# 01_-_MC.net
KiCad netlist of a schematic drawn in Altium Designer
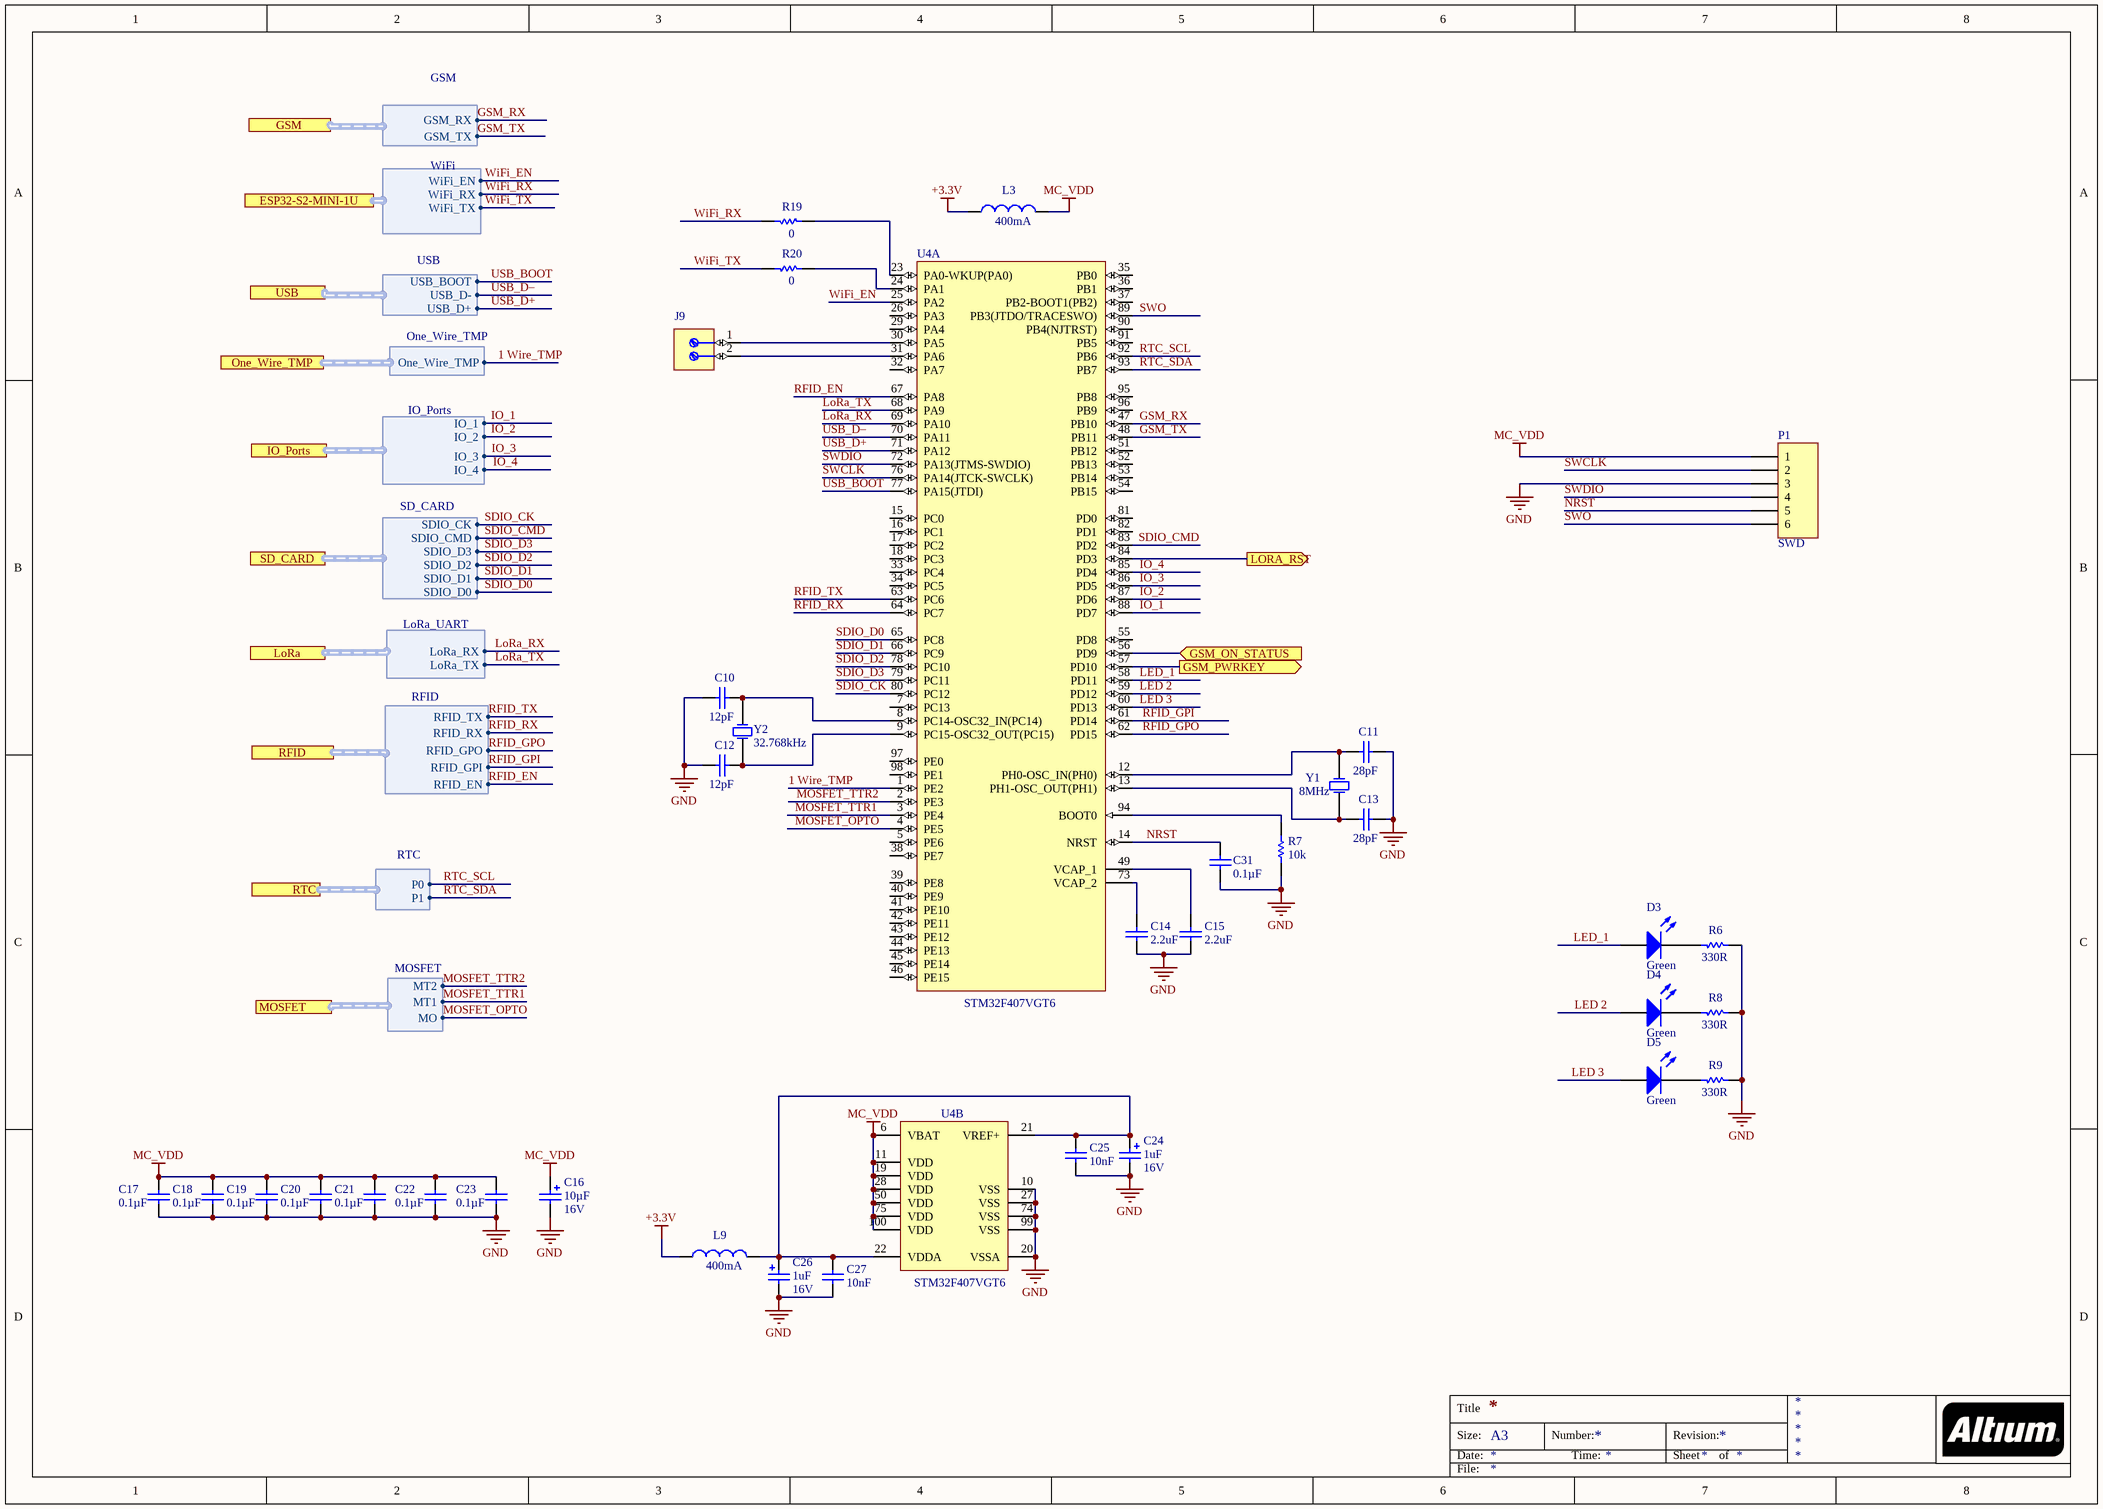
[diagram p0: [01] - MC.SchDoc]

(export (version "E")
  (design (tool "Eeschema 10.0.6"))
  (components
    (comp (ref "C10")
      (value "Capacitor")
      (footprint "Cap 0603")
      (description "Chip Capacitor Nonpolar")
      (fields
        (field (name "MANUFACTURER") "KEMET")
        (field (name "MANUFACTURER PART NUMBER") "C0603C120J5GAC-TU")
        (field (name "CAPACITANCE") "12pF")
      )
      (libsource (lib "Altium_Library") (part "Capacitor"))
    )
    (comp (ref "C11")
      (value "Capacitor")
      (footprint "Cap 0603")
      (description "Chip Capacitor Nonpolar")
      (fields
        (field (name "MANUFACTURER") "KEMET")
        (field (name "MANUFACTURER PART NUMBER") "C0603C180K5GACTU")
        (field (name "CAPACITANCE") "28pF")
      )
      (libsource (lib "Altium_Library") (part "Capacitor"))
    )
    (comp (ref "C12")
      (value "Capacitor")
      (footprint "Cap 0603")
      (description "Chip Capacitor Nonpolar")
      (fields
        (field (name "MANUFACTURER") "KEMET")
        (field (name "MANUFACTURER PART NUMBER") "C0603C120J5GAC-TU")
        (field (name "CAPACITANCE") "12pF")
      )
      (libsource (lib "Altium_Library") (part "Capacitor"))
    )
    (comp (ref "C13")
      (value "Capacitor")
      (footprint "Cap 0603")
      (description "Chip Capacitor Nonpolar")
      (fields
        (field (name "MANUFACTURER") "KEMET")
        (field (name "MANUFACTURER PART NUMBER") "C0603C180K5GACTU")
        (field (name "CAPACITANCE") "28pF")
      )
      (libsource (lib "Altium_Library") (part "Capacitor"))
    )
    (comp (ref "C14")
      (value "Capacitor")
      (footprint "Cap 0603")
      (description "Chip Capacitor Nonpolar")
      (fields
        (field (name "MANUFACTURER") "Samsung")
        (field (name "MANUFACTURER PART NUMBER") "CL21A225KAFNNNG")
        (field (name "CAPACITANCE") "2.2uF")
      )
      (libsource (lib "Altium_Library") (part "Capacitor"))
    )
    (comp (ref "C15")
      (value "Capacitor")
      (footprint "Cap 0603")
      (description "Chip Capacitor Nonpolar")
      (fields
        (field (name "MANUFACTURER") "Samsung")
        (field (name "MANUFACTURER PART NUMBER") "CL21A225KAFNNNG")
        (field (name "CAPACITANCE") "2.2uF")
      )
      (libsource (lib "Altium_Library") (part "Capacitor"))
    )
    (comp (ref "C16")
      (value "Capacitor Polarized")
      (footprint "Tantalum 3216 A")
      (description "Tantalum Capacitor")
      (fields
        (field (name "MANUFACTURER") "Kemet")
        (field (name "MANUFACTURER PART NUMBER") "T491A106K016AT")
        (field (name "CAPACITANCE") "10µF")
        (field (name "VOLTAGE - RATED") "16V")
      )
      (libsource (lib "Altium_Library") (part "Capacitor Polarized"))
    )
    (comp (ref "C17")
      (value "Capacitor")
      (footprint "Cap 0603")
      (description "Chip Capacitor Nonpolar")
      (fields
        (field (name "MANUFACTURER") "Kemet")
        (field (name "MANUFACTURER PART NUMBER") "C0603C104K5RACTU")
        (field (name "CAPACITANCE") "0.1µF")
      )
      (libsource (lib "Altium_Library") (part "Capacitor"))
    )
    (comp (ref "C18")
      (value "Capacitor")
      (footprint "Cap 0603")
      (description "Chip Capacitor Nonpolar")
      (fields
        (field (name "MANUFACTURER") "Kemet")
        (field (name "MANUFACTURER PART NUMBER") "C0603C104K5RACTU")
        (field (name "CAPACITANCE") "0.1µF")
      )
      (libsource (lib "Altium_Library") (part "Capacitor"))
    )
    (comp (ref "C19")
      (value "Capacitor")
      (footprint "Cap 0603")
      (description "Chip Capacitor Nonpolar")
      (fields
        (field (name "MANUFACTURER") "Kemet")
        (field (name "MANUFACTURER PART NUMBER") "C0603C104K5RACTU")
        (field (name "CAPACITANCE") "0.1µF")
      )
      (libsource (lib "Altium_Library") (part "Capacitor"))
    )
    (comp (ref "C20")
      (value "Capacitor")
      (footprint "Cap 0603")
      (description "Chip Capacitor Nonpolar")
      (fields
        (field (name "MANUFACTURER") "Kemet")
        (field (name "MANUFACTURER PART NUMBER") "C0603C104K5RACTU")
        (field (name "CAPACITANCE") "0.1µF")
      )
      (libsource (lib "Altium_Library") (part "Capacitor"))
    )
    (comp (ref "C21")
      (value "Capacitor")
      (footprint "Cap 0603")
      (description "Chip Capacitor Nonpolar")
      (fields
        (field (name "MANUFACTURER") "Kemet")
        (field (name "MANUFACTURER PART NUMBER") "C0603C104K5RACTU")
        (field (name "CAPACITANCE") "0.1µF")
      )
      (libsource (lib "Altium_Library") (part "Capacitor"))
    )
    (comp (ref "C22")
      (value "Capacitor")
      (footprint "Cap 0603")
      (description "Chip Capacitor Nonpolar")
      (fields
        (field (name "MANUFACTURER") "Kemet")
        (field (name "MANUFACTURER PART NUMBER") "C0603C104K5RACTU")
        (field (name "CAPACITANCE") "0.1µF")
      )
      (libsource (lib "Altium_Library") (part "Capacitor"))
    )
    (comp (ref "C23")
      (value "Capacitor")
      (footprint "Cap 0603")
      (description "Chip Capacitor Nonpolar")
      (fields
        (field (name "MANUFACTURER") "Kemet")
        (field (name "MANUFACTURER PART NUMBER") "C0603C104K5RACTU")
        (field (name "CAPACITANCE") "0.1µF")
      )
      (libsource (lib "Altium_Library") (part "Capacitor"))
    )
    (comp (ref "C24")
      (value "Capacitor Polarized")
      (footprint "Tantalum 3216 A")
      (description "Tantalum Capacitor")
      (fields
        (field (name "MANUFACTURER") "Vishay Sprague")
        (field (name "MANUFACTURER PART NUMBER") "293D105X9016A2TE3")
        (field (name "CAPACITANCE") "1uF")
        (field (name "VOLTAGE RATING") "16V")
      )
      (libsource (lib "Altium_Library") (part "Capacitor Polarized"))
    )
    (comp (ref "C25")
      (value "Capacitor")
      (footprint "Cap 0603")
      (description "Chip Capacitor Nonpolar")
      (fields
        (field (name "MANUFACTURER") "Samsung")
        (field (name "MANUFACTURER PART NUMBER") "CL10B103KB8WPNC")
        (field (name "CAPACITANCE") "10nF")
      )
      (libsource (lib "Altium_Library") (part "Capacitor"))
    )
    (comp (ref "C26")
      (value "Capacitor Polarized")
      (footprint "Tantalum 3216 A")
      (description "Tantalum Capacitor")
      (fields
        (field (name "MANUFACTURER") "Vishay Sprague")
        (field (name "MANUFACTURER PART NUMBER") "293D105X9016A2TE3")
        (field (name "CAPACITANCE") "1uF")
        (field (name "VOLTAGE RATING") "16V")
      )
      (libsource (lib "Altium_Library") (part "Capacitor Polarized"))
    )
    (comp (ref "C27")
      (value "Capacitor")
      (footprint "Cap 0603")
      (description "Chip Capacitor Nonpolar")
      (fields
        (field (name "MANUFACTURER") "Samsung")
        (field (name "MANUFACTURER PART NUMBER") "CL10B103KB8WPNC")
        (field (name "CAPACITANCE") "10nF")
      )
      (libsource (lib "Altium_Library") (part "Capacitor"))
    )
    (comp (ref "C31")
      (value "Capacitor")
      (footprint "Cap 0603")
      (description "Chip Capacitor Nonpolar")
      (fields
        (field (name "MANUFACTURER") "Kemet")
        (field (name "MANUFACTURER PART NUMBER") "C0603C104K5RACTU")
        (field (name "CAPACITANCE") "0.1µF")
      )
      (libsource (lib "Altium_Library") (part "Capacitor"))
    )
    (comp (ref "D3")
      (value "LED")
      (footprint "Led 0805 green")
      (description "Led 0805")
      (fields
        (field (name "MANUFACTURER") "Vishay Lite-On")
        (field (name "MANUFACTURER PART NUMBER") "LTST-S220GKT")
        (field (name "COLOUR") "Green")
      )
      (libsource (lib "Altium_Library") (part "LED"))
    )
    (comp (ref "D4")
      (value "LED")
      (footprint "Led 0805 green")
      (description "Led 0805")
      (fields
        (field (name "MANUFACTURER") "Vishay Lite-On")
        (field (name "MANUFACTURER PART NUMBER") "LTST-S220GKT")
        (field (name "COLOUR") "Green")
      )
      (libsource (lib "Altium_Library") (part "LED"))
    )
    (comp (ref "D5")
      (value "LED")
      (footprint "Led 0805 green")
      (description "Led 0805")
      (fields
        (field (name "MANUFACTURER") "Vishay Lite-On")
        (field (name "MANUFACTURER PART NUMBER") "LTST-S220GKT")
        (field (name "COLOUR") "Green")
      )
      (libsource (lib "Altium_Library") (part "LED"))
    )
    (comp (ref "J9")
      (value "~")
      (footprint "Blue Tractor-2021:Connector -PHOENIX_1715721")
      (description "Terminal Block, 2 Positions, Screw Connection")
      (fields
        (field (name "PART NUMBER") "PHOENIX_1715721")
        (field (name "MANUFACTURER") "PHOENIX CONTACT")
        (field (name "AUTHOR") "CERN DEM JLC")
      )
      (libsource (lib "Connectors") (part "Terminal Block_2 Positions_Screw Connection"))
    )
    (comp (ref "L3")
      (value "Inductor")
      (footprint "0603")
      (description "Sumida inductore ferrite core smd")
      (fields
        (field (name "MANUFACTURER") "Murata Electronics North America")
        (field (name "MANUFACTURER PART NUMBER") "BLM18AG102SN1D")
        (field (name "CURRENT RATING (MAX)") "400mA")
      )
      (libsource (lib "Altium_Library") (part "Inductor"))
    )
    (comp (ref "L9")
      (value "Inductor")
      (footprint "0603")
      (description "Sumida inductore ferrite core smd")
      (fields
        (field (name "MANUFACTURER") "Murata Electronics North America")
        (field (name "MANUFACTURER PART NUMBER") "BLM18AG102SN1D")
        (field (name "CURRENT RATING (MAX)") "400mA")
      )
      (libsource (lib "Altium_Library") (part "Inductor"))
    )
    (comp (ref "P1")
      (value "SWD")
      (footprint "HDR1X6")
      (description "Header, 6-Pin")
      (fields (field (name "PUBLISHER") "Altium Limited"))
      (libsource (lib "Miscellaneous Connectors") (part "Header 6"))
    )
    (comp (ref "R6")
      (value "Res1")
      (footprint "Res-0603")
      (description "Chip Resistor")
      (fields
        (field (name "MANUFACTURER") "Panasonic")
        (field (name "MANUFACTURER PART NUMBER") "ERJ-3EKF3300V")
        (field (name "RESISTANCE") "330R")
      )
      (libsource (lib "Altium_Library") (part "Res1"))
    )
    (comp (ref "R7")
      (value "Res1")
      (footprint "Res-0603")
      (description "Chip Resistor")
      (fields
        (field (name "MANUFACTURER") "Panasonic")
        (field (name "MANUFACTURER PART NUMBER") "ERJ-3GEYJ103V")
        (field (name "RESISTANCE") "10k")
      )
      (libsource (lib "Altium_Library") (part "Res1"))
    )
    (comp (ref "R8")
      (value "Res1")
      (footprint "Res-0603")
      (description "Chip Resistor")
      (fields
        (field (name "MANUFACTURER") "Panasonic")
        (field (name "MANUFACTURER PART NUMBER") "ERJ-3EKF3300V")
        (field (name "RESISTANCE") "330R")
      )
      (libsource (lib "Altium_Library") (part "Res1"))
    )
    (comp (ref "R9")
      (value "Res1")
      (footprint "Res-0603")
      (description "Chip Resistor")
      (fields
        (field (name "MANUFACTURER") "Panasonic")
        (field (name "MANUFACTURER PART NUMBER") "ERJ-3EKF3300V")
        (field (name "RESISTANCE") "330R")
      )
      (libsource (lib "Altium_Library") (part "Res1"))
    )
    (comp (ref "R19")
      (value "Res1")
      (footprint "Res-0603")
      (description "Chip Resistor")
      (fields
        (field (name "MANUFACTURER") "Panasonic")
        (field (name "MANUFACTURER PART NUMBER") "ERJ-3EKF3300V")
        (field (name "RESISTANCE") "0")
      )
      (libsource (lib "Altium_Library") (part "Res1"))
    )
    (comp (ref "R20")
      (value "Res1")
      (footprint "Res-0603")
      (description "Chip Resistor")
      (fields
        (field (name "MANUFACTURER") "Panasonic")
        (field (name "MANUFACTURER PART NUMBER") "ERJ-3EKF3300V")
        (field (name "RESISTANCE") "0")
      )
      (libsource (lib "Altium_Library") (part "Res1"))
    )
    (comp (ref "U4")
      (value "STM32F407VGT6J")
      (footprint "LQFP100_N")
      (fields
        (field (name "MANUFACTURER") "STMicroelectronics")
        (field (name "MANUFACTURER PART NUMBER") "STM32F407VGT6")
      )
      (libsource (lib "STMicroelectronics STM32 F4") (part "STM32F407VGT6J"))
    )
    (comp (ref "Y1")
      (value "XTAL2pin")
      (footprint "ABM3")
      (description "Crystal Oscillator")
      (fields
        (field (name "MANUFACTURER") "Abracon Corporation")
        (field (name "MANUFACTURER PART NUMBER") "ABM3-8.000MHZ-D2Y-T")
        (field (name "FREQUENCY") "8MHz")
        (field (name "PUBLISHER") "Ruslan Gimazetdinov")
      )
      (libsource (lib "Altium_Library") (part "XTAL2pin"))
    )
    (comp (ref "Y2")
      (value "32768")
      (footprint "ECX-31B")
      (description "Crystal Oscillator")
      (fields
        (field (name "MANUFACTURER") "ECS International")
        (field (name "MANUFACTURER PART NUMBER") "ECS-.327-12.5-34B-TR")
        (field (name "FREQUENCY") "32.768kHz")
      )
      (libsource (lib "Altium_Library") (part "XTAL2pin"))
    )
  )
  (nets
    (net (code "11") (name "+3.3V") (class "Default")
      (node (ref "L3") (pin "1") (pinfunction "1_1") (pintype "passive"))
      (node (ref "L9") (pin "1") (pinfunction "1_1") (pintype "passive"))
    )
    (net (code "12") (name "/1 Wire_TMP") (class "Default")
      (node (ref "U4") (pin "1") (pinfunction "PE2_1") (pintype "bidirectional"))
    )
    (net (code "13") (name "/GSM_ON_STATUS") (class "Default")
      (node (ref "U4") (pin "56") (pinfunction "PD9_56") (pintype "bidirectional"))
    )
    (net (code "14") (name "/GSM_PWRKEY") (class "Default")
      (node (ref "U4") (pin "57") (pinfunction "PD10_57") (pintype "bidirectional"))
    )
    (net (code "15") (name "/GSM_RX") (class "Default")
      (node (ref "U4") (pin "47") (pinfunction "PB10_47") (pintype "bidirectional"))
    )
    (net (code "16") (name "/GSM_TX") (class "Default")
      (node (ref "U4") (pin "48") (pinfunction "PB11_48") (pintype "bidirectional"))
    )
    (net (code "17") (name "/IO_1") (class "Default")
      (node (ref "U4") (pin "88") (pinfunction "PD7_88") (pintype "bidirectional"))
    )
    (net (code "18") (name "/IO_2") (class "Default")
      (node (ref "U4") (pin "87") (pinfunction "PD6_87") (pintype "bidirectional"))
    )
    (net (code "19") (name "/IO_3") (class "Default")
      (node (ref "U4") (pin "86") (pinfunction "PD5_86") (pintype "bidirectional"))
    )
    (net (code "20") (name "/IO_4") (class "Default")
      (node (ref "U4") (pin "85") (pinfunction "PD4_85") (pintype "bidirectional"))
    )
    (net (code "21") (name "/LED 2") (class "Default")
      (node (ref "D4") (pin "2") (pinfunction "A_2") (pintype "passive"))
      (node (ref "U4") (pin "59") (pinfunction "PD12_59") (pintype "bidirectional"))
    )
    (net (code "22") (name "/LED 3") (class "Default")
      (node (ref "D5") (pin "2") (pinfunction "A_2") (pintype "passive"))
      (node (ref "U4") (pin "60") (pinfunction "PD13_60") (pintype "bidirectional"))
    )
    (net (code "23") (name "/LED_1") (class "Default")
      (node (ref "D3") (pin "2") (pinfunction "A_2") (pintype "passive"))
      (node (ref "U4") (pin "58") (pinfunction "PD11_58") (pintype "bidirectional"))
    )
    (net (code "24") (name "/LORA_RST") (class "Default")
      (node (ref "U4") (pin "84") (pinfunction "PD3_84") (pintype "bidirectional"))
    )
    (net (code "25") (name "/LoRa_RX") (class "Default")
      (node (ref "U4") (pin "69") (pinfunction "PA10_69") (pintype "bidirectional"))
    )
    (net (code "26") (name "/LoRa_TX") (class "Default")
      (node (ref "U4") (pin "68") (pinfunction "PA9_68") (pintype "bidirectional"))
    )
    (net (code "27") (name "/MOSFET_OPTO") (class "Default")
      (node (ref "U4") (pin "4") (pinfunction "PE5_4") (pintype "bidirectional"))
    )
    (net (code "28") (name "/MOSFET_TTR1") (class "Default")
      (node (ref "U4") (pin "3") (pinfunction "PE4_3") (pintype "bidirectional"))
    )
    (net (code "29") (name "/MOSFET_TTR2") (class "Default")
      (node (ref "U4") (pin "2") (pinfunction "PE3_2") (pintype "bidirectional"))
    )
    (net (code "30") (name "/NRST") (class "Default")
      (node (ref "C31") (pin "2") (pinfunction "2_2") (pintype "passive"))
      (node (ref "P1") (pin "5") (pinfunction "5_5") (pintype "passive"))
      (node (ref "U4") (pin "14") (pinfunction "NRST_14") (pintype "bidirectional"))
    )
    (net (code "31") (name "/RFID_EN") (class "Default")
      (node (ref "U4") (pin "67") (pinfunction "PA8_67") (pintype "bidirectional"))
    )
    (net (code "32") (name "/RFID_GPI") (class "Default")
      (node (ref "U4") (pin "61") (pinfunction "PD14_61") (pintype "bidirectional"))
    )
    (net (code "33") (name "/RFID_GPO") (class "Default")
      (node (ref "U4") (pin "62") (pinfunction "PD15_62") (pintype "bidirectional"))
    )
    (net (code "34") (name "/RFID_RX") (class "Default")
      (node (ref "U4") (pin "64") (pinfunction "PC7_64") (pintype "bidirectional"))
    )
    (net (code "35") (name "/RFID_TX") (class "Default")
      (node (ref "U4") (pin "63") (pinfunction "PC6_63") (pintype "bidirectional"))
    )
    (net (code "36") (name "/RTC_SCL") (class "Default")
      (node (ref "U4") (pin "92") (pinfunction "PB6_92") (pintype "bidirectional"))
    )
    (net (code "37") (name "/RTC_SDA") (class "Default")
      (node (ref "U4") (pin "93") (pinfunction "PB7_93") (pintype "bidirectional"))
    )
    (net (code "38") (name "/SDIO_CK") (class "Default")
      (node (ref "U4") (pin "80") (pinfunction "PC12_80") (pintype "bidirectional"))
    )
    (net (code "39") (name "/SDIO_CMD") (class "Default")
      (node (ref "U4") (pin "83") (pinfunction "PD2_83") (pintype "bidirectional"))
    )
    (net (code "40") (name "/SDIO_D0") (class "Default")
      (node (ref "U4") (pin "65") (pinfunction "PC8_65") (pintype "bidirectional"))
    )
    (net (code "41") (name "/SDIO_D1") (class "Default")
      (node (ref "U4") (pin "66") (pinfunction "PC9_66") (pintype "bidirectional"))
    )
    (net (code "42") (name "/SDIO_D2") (class "Default")
      (node (ref "U4") (pin "78") (pinfunction "PC10_78") (pintype "bidirectional"))
    )
    (net (code "43") (name "/SDIO_D3") (class "Default")
      (node (ref "U4") (pin "79") (pinfunction "PC11_79") (pintype "bidirectional"))
    )
    (net (code "44") (name "/SWCLK") (class "Default")
      (node (ref "P1") (pin "2") (pinfunction "2_2") (pintype "passive"))
      (node (ref "U4") (pin "76") (pinfunction "PA14(JTCK-SWCLK)_76") (pintype "bidirectional"))
    )
    (net (code "45") (name "/SWDIO") (class "Default")
      (node (ref "P1") (pin "4") (pinfunction "4_4") (pintype "passive"))
      (node (ref "U4") (pin "72") (pinfunction "PA13(JTMS-SWDIO)_72") (pintype "bidirectional"))
    )
    (net (code "46") (name "/SWO") (class "Default")
      (node (ref "P1") (pin "6") (pinfunction "6_6") (pintype "passive"))
      (node (ref "U4") (pin "89") (pinfunction "PB3(JTDO/TRACESWO)_89") (pintype "bidirectional"))
    )
    (net (code "47") (name "/USB_BOOT") (class "Default")
      (node (ref "U4") (pin "77") (pinfunction "PA15(JTDI)_77") (pintype "bidirectional"))
    )
    (net (code "48") (name "/USB_D+") (class "Default")
      (node (ref "U4") (pin "71") (pinfunction "PA12_71") (pintype "bidirectional"))
    )
    (net (code "49") (name "/USB_D–") (class "Default")
      (node (ref "U4") (pin "70") (pinfunction "PA11_70") (pintype "bidirectional"))
    )
    (net (code "50") (name "/WiFi_EN") (class "Default")
      (node (ref "U4") (pin "25") (pinfunction "PA2_25") (pintype "bidirectional"))
    )
    (net (code "51") (name "/WiFi_RX") (class "Default")
      (node (ref "R19") (pin "1") (pinfunction "1_1") (pintype "passive"))
    )
    (net (code "52") (name "/WiFi_TX") (class "Default")
      (node (ref "R20") (pin "1") (pinfunction "1_1") (pintype "passive"))
    )
    (net (code "63") (name "GND") (class "Default")
      (node (ref "C10") (pin "2") (pinfunction "2_2") (pintype "passive"))
      (node (ref "C11") (pin "2") (pinfunction "2_2") (pintype "passive"))
      (node (ref "C12") (pin "2") (pinfunction "2_2") (pintype "passive"))
      (node (ref "C13") (pin "2") (pinfunction "2_2") (pintype "passive"))
      (node (ref "C14") (pin "1") (pinfunction "1_1") (pintype "passive"))
      (node (ref "C15") (pin "1") (pinfunction "1_1") (pintype "passive"))
      (node (ref "C16") (pin "2") (pinfunction "2_2") (pintype "passive"))
      (node (ref "C17") (pin "1") (pinfunction "1_1") (pintype "passive"))
      (node (ref "C18") (pin "1") (pinfunction "1_1") (pintype "passive"))
      (node (ref "C19") (pin "1") (pinfunction "1_1") (pintype "passive"))
      (node (ref "C20") (pin "1") (pinfunction "1_1") (pintype "passive"))
      (node (ref "C21") (pin "1") (pinfunction "1_1") (pintype "passive"))
      (node (ref "C22") (pin "1") (pinfunction "1_1") (pintype "passive"))
      (node (ref "C23") (pin "1") (pinfunction "1_1") (pintype "passive"))
      (node (ref "C24") (pin "2") (pinfunction "2_2") (pintype "passive"))
      (node (ref "C25") (pin "1") (pinfunction "1_1") (pintype "passive"))
      (node (ref "C26") (pin "2") (pinfunction "2_2") (pintype "passive"))
      (node (ref "C27") (pin "1") (pinfunction "1_1") (pintype "passive"))
      (node (ref "C31") (pin "1") (pinfunction "1_1") (pintype "passive"))
      (node (ref "P1") (pin "3") (pinfunction "3_3") (pintype "passive"))
      (node (ref "R6") (pin "2") (pinfunction "2_2") (pintype "passive"))
      (node (ref "R7") (pin "1") (pinfunction "1_1") (pintype "passive"))
      (node (ref "R8") (pin "2") (pinfunction "2_2") (pintype "passive"))
      (node (ref "R9") (pin "2") (pinfunction "2_2") (pintype "passive"))
      (node (ref "U4") (pin "10") (pinfunction "VSS_10") (pintype "power_in"))
      (node (ref "U4") (pin "20") (pinfunction "VSSA_20") (pintype "power_in"))
      (node (ref "U4") (pin "27") (pinfunction "VSS_27") (pintype "power_in"))
      (node (ref "U4") (pin "74") (pinfunction "VSS_74") (pintype "power_in"))
      (node (ref "U4") (pin "99") (pinfunction "VSS_99") (pintype "power_in"))
    )
    (net (code "64") (name "MC_VDD") (class "Default")
      (node (ref "C16") (pin "1") (pinfunction "1_1") (pintype "passive"))
      (node (ref "C17") (pin "2") (pinfunction "2_2") (pintype "passive"))
      (node (ref "C18") (pin "2") (pinfunction "2_2") (pintype "passive"))
      (node (ref "C19") (pin "2") (pinfunction "2_2") (pintype "passive"))
      (node (ref "C20") (pin "2") (pinfunction "2_2") (pintype "passive"))
      (node (ref "C21") (pin "2") (pinfunction "2_2") (pintype "passive"))
      (node (ref "C22") (pin "2") (pinfunction "2_2") (pintype "passive"))
      (node (ref "C23") (pin "2") (pinfunction "2_2") (pintype "passive"))
      (node (ref "L3") (pin "2") (pinfunction "2_2") (pintype "passive"))
      (node (ref "P1") (pin "1") (pinfunction "1_1") (pintype "passive"))
      (node (ref "U4") (pin "100") (pinfunction "VDD_100") (pintype "power_in"))
      (node (ref "U4") (pin "11") (pinfunction "VDD_11") (pintype "power_in"))
      (node (ref "U4") (pin "19") (pinfunction "VDD_19") (pintype "power_in"))
      (node (ref "U4") (pin "28") (pinfunction "VDD_28") (pintype "power_in"))
      (node (ref "U4") (pin "50") (pinfunction "VDD_50") (pintype "power_in"))
      (node (ref "U4") (pin "6") (pinfunction "VBAT_6") (pintype "power_in"))
      (node (ref "U4") (pin "75") (pinfunction "VDD_75") (pintype "power_in"))
    )
    (net (code "65") (name "Net-(D3-K)") (class "Default")
      (node (ref "D3") (pin "1") (pinfunction "K_1") (pintype "passive"))
      (node (ref "R6") (pin "1") (pinfunction "1_1") (pintype "passive"))
    )
    (net (code "66") (name "Net-(D4-K)") (class "Default")
      (node (ref "D4") (pin "1") (pinfunction "K_1") (pintype "passive"))
      (node (ref "R8") (pin "1") (pinfunction "1_1") (pintype "passive"))
    )
    (net (code "67") (name "Net-(D5-K)") (class "Default")
      (node (ref "D5") (pin "1") (pinfunction "K_1") (pintype "passive"))
      (node (ref "R9") (pin "1") (pinfunction "1_1") (pintype "passive"))
    )
    (net (code "68") (name "Net-(U4A-BOOT0)") (class "Default")
      (node (ref "R7") (pin "2") (pinfunction "2_2") (pintype "passive"))
      (node (ref "U4") (pin "94") (pinfunction "BOOT0_94") (pintype "input"))
    )
    (net (code "69") (name "Net-(U4A-PA0-WKUP(PA0))") (class "Default")
      (node (ref "R19") (pin "2") (pinfunction "2_2") (pintype "passive"))
      (node (ref "U4") (pin "23") (pinfunction "PA0-WKUP(PA0)_23") (pintype "bidirectional"))
    )
    (net (code "70") (name "Net-(U4A-PA1)") (class "Default")
      (node (ref "R20") (pin "2") (pinfunction "2_2") (pintype "passive"))
      (node (ref "U4") (pin "24") (pinfunction "PA1_24") (pintype "bidirectional"))
    )
    (net (code "71") (name "Net-(U4A-PA5)") (class "Default")
      (node (ref "J9") (pin "1") (pinfunction "1_1") (pintype "bidirectional"))
      (node (ref "U4") (pin "30") (pinfunction "PA5_30") (pintype "bidirectional"))
    )
    (net (code "72") (name "Net-(U4A-PA6)") (class "Default")
      (node (ref "J9") (pin "2") (pinfunction "2_2") (pintype "bidirectional"))
      (node (ref "U4") (pin "31") (pinfunction "PA6_31") (pintype "bidirectional"))
    )
    (net (code "73") (name "Net-(U4A-PC14-OSC32_IN(PC14))") (class "Default")
      (node (ref "C10") (pin "1") (pinfunction "1_1") (pintype "passive"))
      (node (ref "U4") (pin "8") (pinfunction "PC14-OSC32_IN(PC14)_8") (pintype "bidirectional"))
      (node (ref "Y2") (pin "2") (pinfunction "OSC2_2") (pintype "passive"))
    )
    (net (code "74") (name "Net-(U4A-PC15-OSC32_OUT(PC15))") (class "Default")
      (node (ref "C12") (pin "1") (pinfunction "1_1") (pintype "passive"))
      (node (ref "U4") (pin "9") (pinfunction "PC15-OSC32_OUT(PC15)_9") (pintype "bidirectional"))
      (node (ref "Y2") (pin "1") (pinfunction "OSC1_1") (pintype "passive"))
    )
    (net (code "75") (name "Net-(U4A-PH0-OSC_IN(PH0))") (class "Default")
      (node (ref "C11") (pin "1") (pinfunction "1_1") (pintype "passive"))
      (node (ref "U4") (pin "12") (pinfunction "PH0-OSC_IN(PH0)_12") (pintype "bidirectional"))
      (node (ref "Y1") (pin "2") (pinfunction "OSC2_2") (pintype "passive"))
    )
    (net (code "76") (name "Net-(U4A-PH1-OSC_OUT(PH1))") (class "Default")
      (node (ref "C13") (pin "1") (pinfunction "1_1") (pintype "passive"))
      (node (ref "U4") (pin "13") (pinfunction "PH1-OSC_OUT(PH1)_13") (pintype "bidirectional"))
      (node (ref "Y1") (pin "1") (pinfunction "OSC1_1") (pintype "passive"))
    )
    (net (code "77") (name "Net-(U4A-VCAP_1)") (class "Default")
      (node (ref "C15") (pin "2") (pinfunction "2_2") (pintype "passive"))
      (node (ref "U4") (pin "49") (pinfunction "VCAP_1_49") (pintype "power_in"))
    )
    (net (code "78") (name "Net-(U4A-VCAP_2)") (class "Default")
      (node (ref "C14") (pin "2") (pinfunction "2_2") (pintype "passive"))
      (node (ref "U4") (pin "73") (pinfunction "VCAP_2_73") (pintype "power_in"))
    )
    (net (code "79") (name "Net-(U4B-VDDA)") (class "Default")
      (node (ref "C24") (pin "1") (pinfunction "1_1") (pintype "passive"))
      (node (ref "C25") (pin "2") (pinfunction "2_2") (pintype "passive"))
      (node (ref "C26") (pin "1") (pinfunction "1_1") (pintype "passive"))
      (node (ref "C27") (pin "2") (pinfunction "2_2") (pintype "passive"))
      (node (ref "L9") (pin "2") (pinfunction "2_2") (pintype "passive"))
      (node (ref "U4") (pin "21") (pinfunction "VREF+_21") (pintype "power_in"))
      (node (ref "U4") (pin "22") (pinfunction "VDDA_22") (pintype "power_in"))
    )
    (net (code "80") (name "unconnected-(U4A-PA3-Pad26)") (class "Default")
      (node (ref "U4") (pin "26") (pinfunction "PA3_26") (pintype "bidirectional"))
    )
    (net (code "81") (name "unconnected-(U4A-PA4-Pad29)") (class "Default")
      (node (ref "U4") (pin "29") (pinfunction "PA4_29") (pintype "bidirectional"))
    )
    (net (code "82") (name "unconnected-(U4A-PA7-Pad32)") (class "Default")
      (node (ref "U4") (pin "32") (pinfunction "PA7_32") (pintype "bidirectional"))
    )
    (net (code "83") (name "unconnected-(U4A-PB0-Pad35)") (class "Default")
      (node (ref "U4") (pin "35") (pinfunction "PB0_35") (pintype "bidirectional"))
    )
    (net (code "84") (name "unconnected-(U4A-PB1-Pad36)") (class "Default")
      (node (ref "U4") (pin "36") (pinfunction "PB1_36") (pintype "bidirectional"))
    )
    (net (code "85") (name "unconnected-(U4A-PB2-BOOT1(PB2)-Pad37)") (class "Default")
      (node (ref "U4") (pin "37") (pinfunction "PB2-BOOT1(PB2)_37") (pintype "bidirectional"))
    )
    (net (code "86") (name "unconnected-(U4A-PB4(NJTRST)-Pad90)") (class "Default")
      (node (ref "U4") (pin "90") (pinfunction "PB4(NJTRST)_90") (pintype "bidirectional"))
    )
    (net (code "87") (name "unconnected-(U4A-PB5-Pad91)") (class "Default")
      (node (ref "U4") (pin "91") (pinfunction "PB5_91") (pintype "bidirectional"))
    )
    (net (code "88") (name "unconnected-(U4A-PB8-Pad95)") (class "Default")
      (node (ref "U4") (pin "95") (pinfunction "PB8_95") (pintype "bidirectional"))
    )
    (net (code "89") (name "unconnected-(U4A-PB9-Pad96)") (class "Default")
      (node (ref "U4") (pin "96") (pinfunction "PB9_96") (pintype "bidirectional"))
    )
    (net (code "90") (name "unconnected-(U4A-PB12-Pad51)") (class "Default")
      (node (ref "U4") (pin "51") (pinfunction "PB12_51") (pintype "bidirectional"))
    )
    (net (code "91") (name "unconnected-(U4A-PB13-Pad52)") (class "Default")
      (node (ref "U4") (pin "52") (pinfunction "PB13_52") (pintype "bidirectional"))
    )
    (net (code "92") (name "unconnected-(U4A-PB14-Pad53)") (class "Default")
      (node (ref "U4") (pin "53") (pinfunction "PB14_53") (pintype "bidirectional"))
    )
    (net (code "93") (name "unconnected-(U4A-PB15-Pad54)") (class "Default")
      (node (ref "U4") (pin "54") (pinfunction "PB15_54") (pintype "bidirectional"))
    )
    (net (code "94") (name "unconnected-(U4A-PC0-Pad15)") (class "Default")
      (node (ref "U4") (pin "15") (pinfunction "PC0_15") (pintype "bidirectional"))
    )
    (net (code "95") (name "unconnected-(U4A-PC1-Pad16)") (class "Default")
      (node (ref "U4") (pin "16") (pinfunction "PC1_16") (pintype "bidirectional"))
    )
    (net (code "96") (name "unconnected-(U4A-PC2-Pad17)") (class "Default")
      (node (ref "U4") (pin "17") (pinfunction "PC2_17") (pintype "bidirectional"))
    )
    (net (code "97") (name "unconnected-(U4A-PC3-Pad18)") (class "Default")
      (node (ref "U4") (pin "18") (pinfunction "PC3_18") (pintype "bidirectional"))
    )
    (net (code "98") (name "unconnected-(U4A-PC4-Pad33)") (class "Default")
      (node (ref "U4") (pin "33") (pinfunction "PC4_33") (pintype "bidirectional"))
    )
    (net (code "99") (name "unconnected-(U4A-PC5-Pad34)") (class "Default")
      (node (ref "U4") (pin "34") (pinfunction "PC5_34") (pintype "bidirectional"))
    )
    (net (code "100") (name "unconnected-(U4A-PC13-Pad7)") (class "Default")
      (node (ref "U4") (pin "7") (pinfunction "PC13_7") (pintype "bidirectional"))
    )
    (net (code "101") (name "unconnected-(U4A-PD0-Pad81)") (class "Default")
      (node (ref "U4") (pin "81") (pinfunction "PD0_81") (pintype "bidirectional"))
    )
    (net (code "102") (name "unconnected-(U4A-PD1-Pad82)") (class "Default")
      (node (ref "U4") (pin "82") (pinfunction "PD1_82") (pintype "bidirectional"))
    )
    (net (code "103") (name "unconnected-(U4A-PD8-Pad55)") (class "Default")
      (node (ref "U4") (pin "55") (pinfunction "PD8_55") (pintype "bidirectional"))
    )
    (net (code "104") (name "unconnected-(U4A-PE0-Pad97)") (class "Default")
      (node (ref "U4") (pin "97") (pinfunction "PE0_97") (pintype "bidirectional"))
    )
    (net (code "105") (name "unconnected-(U4A-PE1-Pad98)") (class "Default")
      (node (ref "U4") (pin "98") (pinfunction "PE1_98") (pintype "bidirectional"))
    )
    (net (code "106") (name "unconnected-(U4A-PE6-Pad5)") (class "Default")
      (node (ref "U4") (pin "5") (pinfunction "PE6_5") (pintype "bidirectional"))
    )
    (net (code "107") (name "unconnected-(U4A-PE7-Pad38)") (class "Default")
      (node (ref "U4") (pin "38") (pinfunction "PE7_38") (pintype "bidirectional"))
    )
    (net (code "108") (name "unconnected-(U4A-PE8-Pad39)") (class "Default")
      (node (ref "U4") (pin "39") (pinfunction "PE8_39") (pintype "bidirectional"))
    )
    (net (code "109") (name "unconnected-(U4A-PE9-Pad40)") (class "Default")
      (node (ref "U4") (pin "40") (pinfunction "PE9_40") (pintype "bidirectional"))
    )
    (net (code "110") (name "unconnected-(U4A-PE10-Pad41)") (class "Default")
      (node (ref "U4") (pin "41") (pinfunction "PE10_41") (pintype "bidirectional"))
    )
    (net (code "111") (name "unconnected-(U4A-PE11-Pad42)") (class "Default")
      (node (ref "U4") (pin "42") (pinfunction "PE11_42") (pintype "bidirectional"))
    )
    (net (code "112") (name "unconnected-(U4A-PE12-Pad43)") (class "Default")
      (node (ref "U4") (pin "43") (pinfunction "PE12_43") (pintype "bidirectional"))
    )
    (net (code "113") (name "unconnected-(U4A-PE13-Pad44)") (class "Default")
      (node (ref "U4") (pin "44") (pinfunction "PE13_44") (pintype "bidirectional"))
    )
    (net (code "114") (name "unconnected-(U4A-PE14-Pad45)") (class "Default")
      (node (ref "U4") (pin "45") (pinfunction "PE14_45") (pintype "bidirectional"))
    )
    (net (code "115") (name "unconnected-(U4A-PE15-Pad46)") (class "Default")
      (node (ref "U4") (pin "46") (pinfunction "PE15_46") (pintype "bidirectional"))
    )
  )
)
